# ArduinoShield.net
KiCad netlist of a schematic drawn in EAGLE
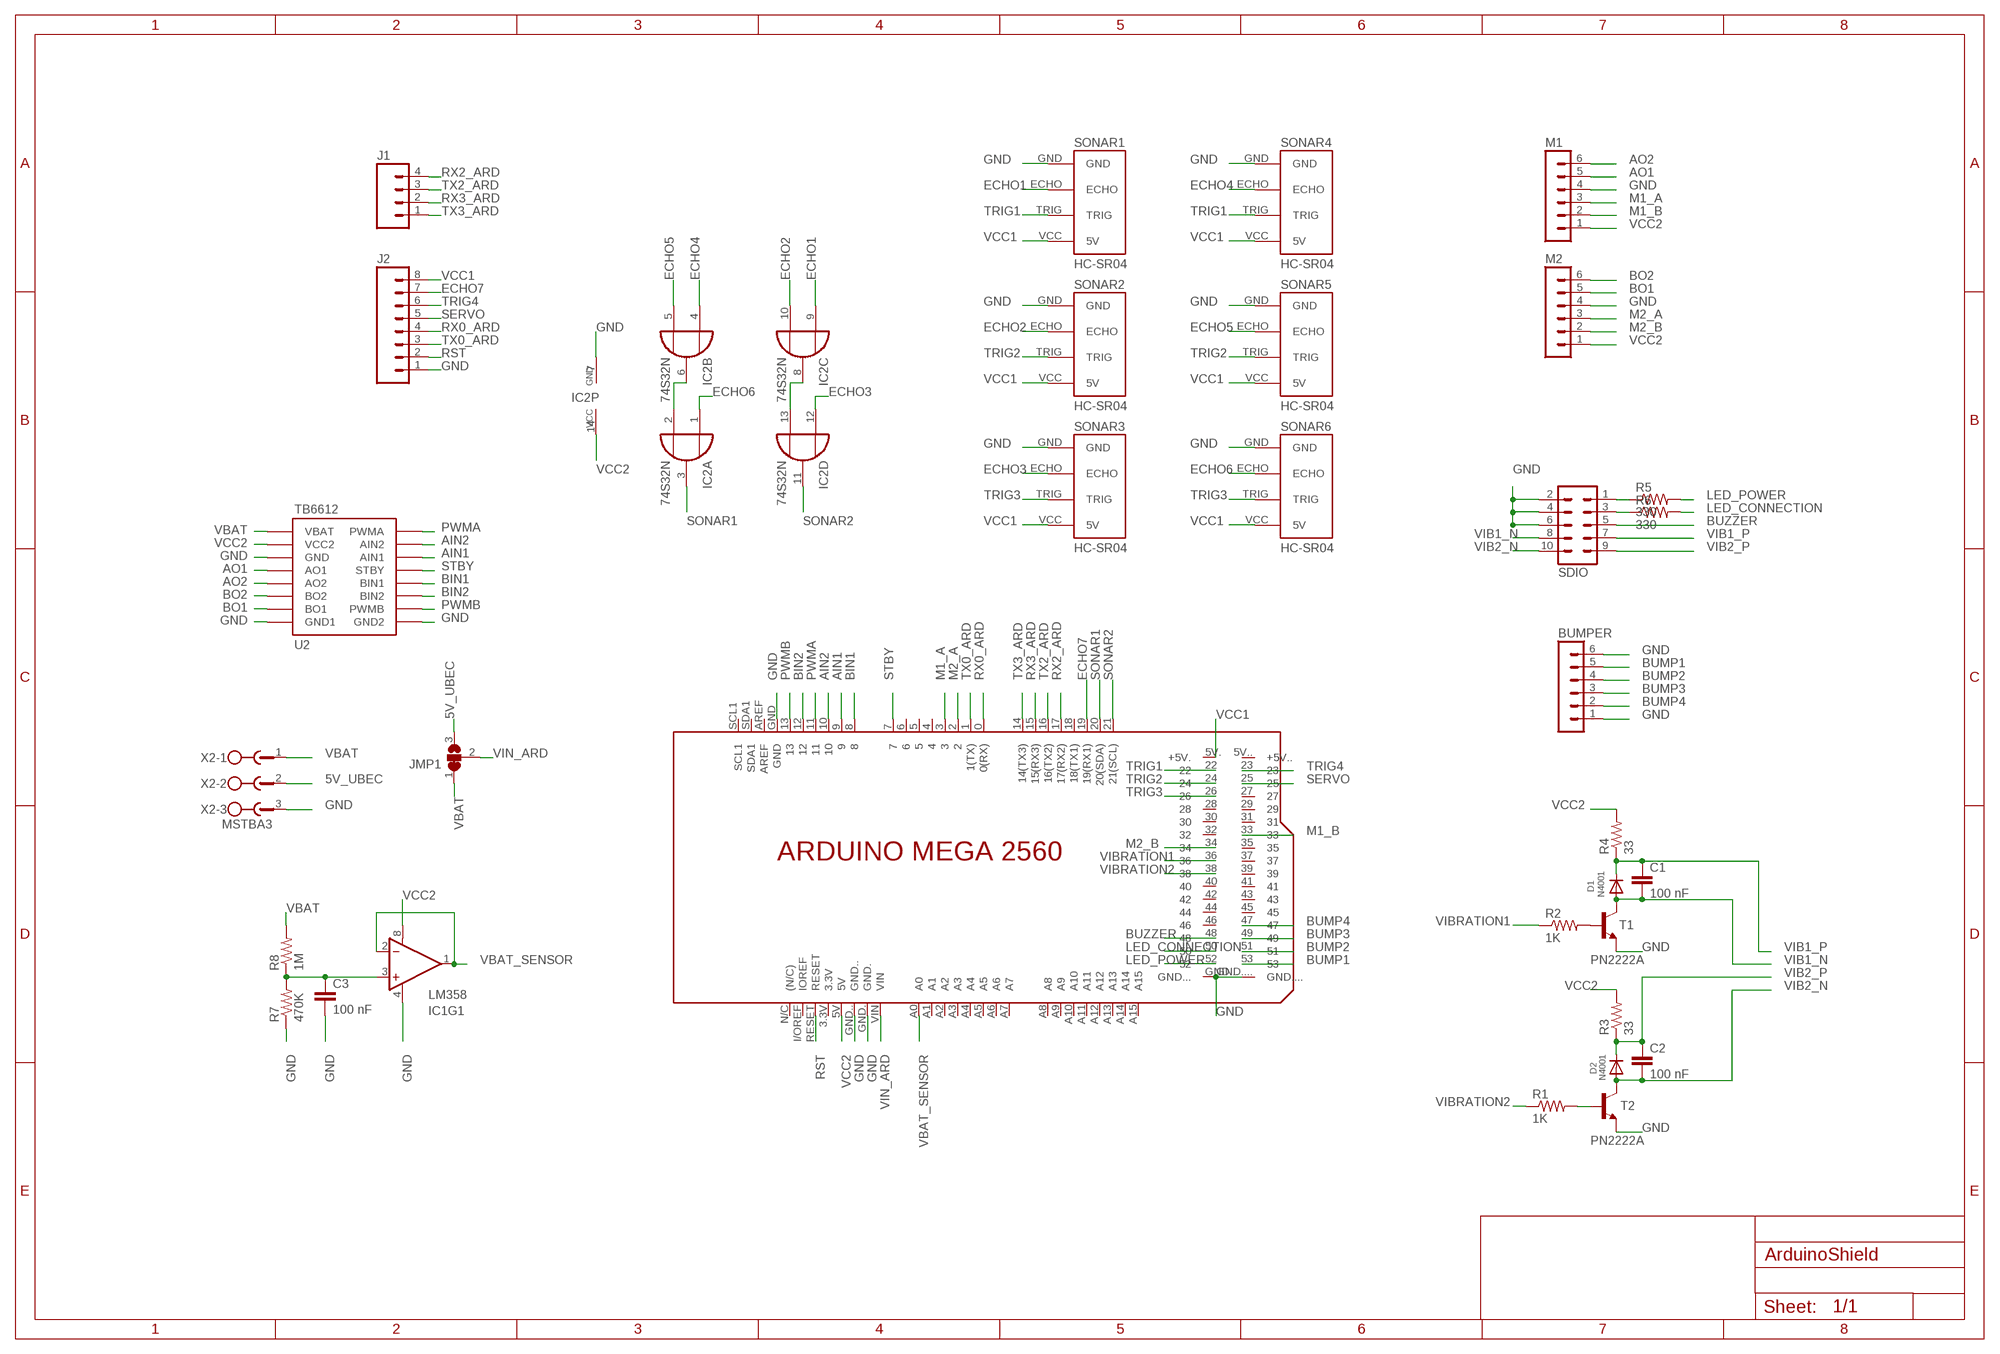
[diagram p0: schematic, sheet 1]

(export (version "E")
  (design (tool "Eeschema 10.0.6"))
  (components
    (comp (ref "BUMPER")
      (value "MA06-1")
      (footprint "eagle-import:MA06-1")
      (libsource (lib "eagle-import") (part "MA06-1"))
    )
    (comp (ref "C1")
      (value "100 nF")
      (footprint "eagle-import:C5B2.5")
      (libsource (lib "eagle-import") (part "C5/2.5"))
    )
    (comp (ref "C2")
      (value "100 nF")
      (footprint "eagle-import:C5B2.5")
      (libsource (lib "eagle-import") (part "C5/2.5"))
    )
    (comp (ref "C3")
      (value "100 nF")
      (footprint "eagle-import:C5B2.5")
      (libsource (lib "eagle-import") (part "C5/2.5"))
    )
    (comp (ref "D1")
      (value "N4001")
      (footprint "eagle-import:DO-1N4148")
      (libsource (lib "eagle-import") (part "DIODEDO-1N4148"))
    )
    (comp (ref "D2")
      (value "N4001")
      (footprint "eagle-import:DO-1N4148")
      (libsource (lib "eagle-import") (part "DIODEDO-1N4148"))
    )
    (comp (ref "IC1")
      (value "LM358")
      (footprint "eagle-import:DIP08")
      (libsource (lib "eagle-import") (part "LM358"))
    )
    (comp (ref "IC2")
      (value "74S32N")
      (footprint "eagle-import:DIL14")
      (libsource (lib "eagle-import") (part "7432NS"))
    )
    (comp (ref "J1")
      (value "M04PTH")
      (footprint "eagle-import:1X04")
      (libsource (lib "eagle-import") (part "M04PTH"))
    )
    (comp (ref "J2")
      (value "M08SILK_FEMALE_PTH")
      (footprint "eagle-import:1X08")
      (libsource (lib "eagle-import") (part "M08SILK_FEMALE_PTH"))
    )
    (comp (ref "JMP1")
      (value "SJ2W")
      (footprint "eagle-import:SJ_2")
      (libsource (lib "eagle-import") (part "SJ2W"))
    )
    (comp (ref "M1")
      (value "MA06-1")
      (footprint "eagle-import:MA06-1")
      (libsource (lib "eagle-import") (part "MA06-1"))
    )
    (comp (ref "M2")
      (value "MA06-1")
      (footprint "eagle-import:MA06-1")
      (libsource (lib "eagle-import") (part "MA06-1"))
    )
    (comp (ref "PCB1")
      (value "ARDUINO_MEGA2560")
      (footprint "eagle-import:ARDUINO_MEGA2560")
      (libsource (lib "eagle-import") (part "ARDUINO_MEGA2560"))
    )
    (comp (ref "R1")
      (value "1K")
      (footprint "eagle-import:0207_2V")
      (libsource (lib "eagle-import") (part "R-US_0207/2V"))
    )
    (comp (ref "R2")
      (value "1K")
      (footprint "eagle-import:0207_2V")
      (libsource (lib "eagle-import") (part "R-US_0207/2V"))
    )
    (comp (ref "R3")
      (value "33")
      (footprint "eagle-import:0207_2V")
      (libsource (lib "eagle-import") (part "R-US_0207/2V"))
    )
    (comp (ref "R4")
      (value "33")
      (footprint "eagle-import:0207_2V")
      (libsource (lib "eagle-import") (part "R-US_0207/2V"))
    )
    (comp (ref "R5")
      (value "330")
      (footprint "eagle-import:0207_2V")
      (libsource (lib "eagle-import") (part "R-US_0207/2V"))
    )
    (comp (ref "R6")
      (value "330")
      (footprint "eagle-import:0207_2V")
      (libsource (lib "eagle-import") (part "R-US_0207/2V"))
    )
    (comp (ref "R7")
      (value "470K")
      (footprint "eagle-import:0207_2V")
      (libsource (lib "eagle-import") (part "R-US_0207/2V"))
    )
    (comp (ref "R8")
      (value "1M")
      (footprint "eagle-import:0207_2V")
      (libsource (lib "eagle-import") (part "R-US_0207/2V"))
    )
    (comp (ref "SDIO")
      (value "MA05-2")
      (footprint "eagle-import:MA05-2")
      (libsource (lib "eagle-import") (part "MA05-2"))
    )
    (comp (ref "SONAR1")
      (value "HC-SR04")
      (footprint "eagle-import:HC-SR04_FOOTPRINT")
      (libsource (lib "eagle-import") (part "HC-SR04"))
    )
    (comp (ref "SONAR2")
      (value "HC-SR04")
      (footprint "eagle-import:HC-SR04_FOOTPRINT")
      (libsource (lib "eagle-import") (part "HC-SR04"))
    )
    (comp (ref "SONAR3")
      (value "HC-SR04")
      (footprint "eagle-import:HC-SR04_FOOTPRINT")
      (libsource (lib "eagle-import") (part "HC-SR04"))
    )
    (comp (ref "SONAR4")
      (value "HC-SR04")
      (footprint "eagle-import:HC-SR04_FOOTPRINT")
      (libsource (lib "eagle-import") (part "HC-SR04"))
    )
    (comp (ref "SONAR5")
      (value "HC-SR04")
      (footprint "eagle-import:HC-SR04_FOOTPRINT")
      (libsource (lib "eagle-import") (part "HC-SR04"))
    )
    (comp (ref "SONAR6")
      (value "HC-SR04")
      (footprint "eagle-import:HC-SR04_FOOTPRINT")
      (libsource (lib "eagle-import") (part "HC-SR04"))
    )
    (comp (ref "T1")
      (value "PN2222A")
      (footprint "eagle-import:TO92-EBC-OVAL")
      (libsource (lib "eagle-import") (part "2N2222"))
    )
    (comp (ref "T2")
      (value "PN2222A")
      (footprint "eagle-import:TO92-EBC-OVAL")
      (libsource (lib "eagle-import") (part "2N2222"))
    )
    (comp (ref "U2")
      (value "TB6612")
      (footprint "eagle-import:TB6612")
      (libsource (lib "eagle-import") (part "TB6612"))
    )
    (comp (ref "X2")
      (value "MSTBA3")
      (footprint "eagle-import:MSTBA3")
      (fields (field (name "MF") "FARNELL") (field (name "MPN") "1757255"))
      (libsource (lib "eagle-import") (part "MSTBA3"))
    )
  )
  (nets
    (net (code "1") (name "/5V_UBEC") (class "Default")
      (node (ref "JMP1") (pin "3") (pinfunction "3_3") (pintype "passive"))
      (node (ref "X2") (pin "2") (pinfunction "1_2") (pintype "passive"))
    )
    (net (code "2") (name "/AIN1") (class "Default")
      (node (ref "PCB1") (pin "9") (pinfunction "9_9") (pintype "bidirectional"))
      (node (ref "U2") (pin "P$14") (pinfunction "AIN1_P$14") (pintype "bidirectional"))
    )
    (net (code "3") (name "/AIN2") (class "Default")
      (node (ref "PCB1") (pin "10") (pinfunction "10_10") (pintype "bidirectional"))
      (node (ref "U2") (pin "P$15") (pinfunction "AIN2_P$15") (pintype "bidirectional"))
    )
    (net (code "4") (name "/AO1") (class "Default")
      (node (ref "M1") (pin "5") (pinfunction "5_5") (pintype "passive"))
      (node (ref "U2") (pin "P$4") (pinfunction "AO1_P$4") (pintype "bidirectional"))
    )
    (net (code "5") (name "/AO2") (class "Default")
      (node (ref "M1") (pin "6") (pinfunction "6_6") (pintype "passive"))
      (node (ref "U2") (pin "P$5") (pinfunction "AO2_P$5") (pintype "bidirectional"))
    )
    (net (code "6") (name "/BIN1") (class "Default")
      (node (ref "PCB1") (pin "8") (pinfunction "8_8") (pintype "bidirectional"))
      (node (ref "U2") (pin "P$12") (pinfunction "BIN1_P$12") (pintype "bidirectional"))
    )
    (net (code "7") (name "/BIN2") (class "Default")
      (node (ref "PCB1") (pin "12") (pinfunction "12_12") (pintype "bidirectional"))
      (node (ref "U2") (pin "P$11") (pinfunction "BIN2_P$11") (pintype "bidirectional"))
    )
    (net (code "8") (name "/BO1") (class "Default")
      (node (ref "M2") (pin "5") (pinfunction "5_5") (pintype "passive"))
      (node (ref "U2") (pin "P$7") (pinfunction "BO1_P$7") (pintype "bidirectional"))
    )
    (net (code "9") (name "/BO2") (class "Default")
      (node (ref "M2") (pin "6") (pinfunction "6_6") (pintype "passive"))
      (node (ref "U2") (pin "P$6") (pinfunction "BO2_P$6") (pintype "bidirectional"))
    )
    (net (code "10") (name "/BUMP1") (class "Default")
      (node (ref "BUMPER") (pin "5") (pinfunction "5_5") (pintype "passive"))
      (node (ref "PCB1") (pin "53") (pinfunction "53_53") (pintype "bidirectional"))
    )
    (net (code "11") (name "/BUMP2") (class "Default")
      (node (ref "BUMPER") (pin "4") (pinfunction "4_4") (pintype "passive"))
      (node (ref "PCB1") (pin "51") (pinfunction "51_51") (pintype "bidirectional"))
    )
    (net (code "12") (name "/BUMP3") (class "Default")
      (node (ref "BUMPER") (pin "3") (pinfunction "3_3") (pintype "passive"))
      (node (ref "PCB1") (pin "49") (pinfunction "49_49") (pintype "bidirectional"))
    )
    (net (code "13") (name "/BUMP4") (class "Default")
      (node (ref "BUMPER") (pin "2") (pinfunction "2_2") (pintype "passive"))
      (node (ref "PCB1") (pin "47") (pinfunction "47_47") (pintype "bidirectional"))
    )
    (net (code "14") (name "/BUZZER") (class "Default")
      (node (ref "PCB1") (pin "48") (pinfunction "48_48") (pintype "bidirectional"))
      (node (ref "SDIO") (pin "5") (pinfunction "5_5") (pintype "passive"))
    )
    (net (code "15") (name "/ECHO1") (class "Default")
      (node (ref "IC2") (pin "9") (pinfunction "I0_9") (pintype "input"))
      (node (ref "SONAR1") (pin "ECHO") (pinfunction "ECHO_ECHO") (pintype "bidirectional"))
    )
    (net (code "16") (name "/ECHO2") (class "Default")
      (node (ref "IC2") (pin "10") (pinfunction "I1_10") (pintype "input"))
      (node (ref "SONAR2") (pin "ECHO") (pinfunction "ECHO_ECHO") (pintype "bidirectional"))
    )
    (net (code "17") (name "/ECHO3") (class "Default")
      (node (ref "IC2") (pin "12") (pinfunction "I0_12") (pintype "input"))
      (node (ref "SONAR3") (pin "ECHO") (pinfunction "ECHO_ECHO") (pintype "bidirectional"))
    )
    (net (code "18") (name "/ECHO4") (class "Default")
      (node (ref "IC2") (pin "4") (pinfunction "I0_4") (pintype "input"))
      (node (ref "SONAR4") (pin "ECHO") (pinfunction "ECHO_ECHO") (pintype "bidirectional"))
    )
    (net (code "19") (name "/ECHO5") (class "Default")
      (node (ref "IC2") (pin "5") (pinfunction "I1_5") (pintype "input"))
      (node (ref "SONAR5") (pin "ECHO") (pinfunction "ECHO_ECHO") (pintype "bidirectional"))
    )
    (net (code "20") (name "/ECHO6") (class "Default")
      (node (ref "IC2") (pin "1") (pinfunction "I0_1") (pintype "input"))
      (node (ref "SONAR6") (pin "ECHO") (pinfunction "ECHO_ECHO") (pintype "bidirectional"))
    )
    (net (code "21") (name "/ECHO7") (class "Default")
      (node (ref "J2") (pin "7") (pinfunction "7_7") (pintype "passive"))
      (node (ref "PCB1") (pin "19") (pinfunction "19(RX1)_19") (pintype "bidirectional"))
    )
    (net (code "22") (name "/GND") (class "Default")
      (node (ref "BUMPER") (pin "1") (pinfunction "1_1") (pintype "passive"))
      (node (ref "BUMPER") (pin "6") (pinfunction "6_6") (pintype "passive"))
      (node (ref "C3") (pin "2") (pinfunction "2_2") (pintype "passive"))
      (node (ref "IC1") (pin "4") (pinfunction "V-_4") (pintype "power_in"))
      (node (ref "IC2") (pin "7") (pinfunction "GND_7") (pintype "power_in"))
      (node (ref "J2") (pin "1") (pinfunction "1_1") (pintype "passive"))
      (node (ref "M1") (pin "4") (pinfunction "4_4") (pintype "passive"))
      (node (ref "M2") (pin "4") (pinfunction "4_4") (pintype "passive"))
      (node (ref "PCB1") (pin "GND") (pinfunction "GND_GND") (pintype "bidirectional"))
      (node (ref "PCB1") (pin "GND.") (pinfunction "GND._GND.") (pintype "bidirectional"))
      (node (ref "PCB1") (pin "GND..") (pinfunction "GND.._GND..") (pintype "bidirectional"))
      (node (ref "PCB1") (pin "GND...") (pinfunction "GND..._GND...") (pintype "bidirectional"))
      (node (ref "PCB1") (pin "GND....") (pinfunction "GND...._GND....") (pintype "bidirectional"))
      (node (ref "R7") (pin "1") (pinfunction "1_1") (pintype "passive"))
      (node (ref "SDIO") (pin "2") (pinfunction "2_2") (pintype "passive"))
      (node (ref "SDIO") (pin "4") (pinfunction "4_4") (pintype "passive"))
      (node (ref "SDIO") (pin "6") (pinfunction "6_6") (pintype "passive"))
      (node (ref "SONAR1") (pin "GND") (pinfunction "GND_GND") (pintype "bidirectional"))
      (node (ref "SONAR2") (pin "GND") (pinfunction "GND_GND") (pintype "bidirectional"))
      (node (ref "SONAR3") (pin "GND") (pinfunction "GND_GND") (pintype "bidirectional"))
      (node (ref "SONAR4") (pin "GND") (pinfunction "GND_GND") (pintype "bidirectional"))
      (node (ref "SONAR5") (pin "GND") (pinfunction "GND_GND") (pintype "bidirectional"))
      (node (ref "SONAR6") (pin "GND") (pinfunction "GND_GND") (pintype "bidirectional"))
      (node (ref "T1") (pin "E") (pinfunction "E_E") (pintype "passive"))
      (node (ref "T2") (pin "E") (pinfunction "E_E") (pintype "passive"))
      (node (ref "U2") (pin "P$3") (pinfunction "GND_P$3") (pintype "bidirectional"))
      (node (ref "U2") (pin "P$8") (pinfunction "GND1_P$8") (pintype "bidirectional"))
      (node (ref "U2") (pin "P$9") (pinfunction "GND2_P$9") (pintype "bidirectional"))
      (node (ref "X2") (pin "3") (pinfunction "1_3") (pintype "passive"))
    )
    (net (code "23") (name "/LED_CONNECTION") (class "Default")
      (node (ref "PCB1") (pin "50") (pinfunction "50_50") (pintype "bidirectional"))
      (node (ref "R6") (pin "2") (pinfunction "2_2") (pintype "passive"))
    )
    (net (code "24") (name "/LED_POWER") (class "Default")
      (node (ref "PCB1") (pin "52") (pinfunction "52_52") (pintype "bidirectional"))
      (node (ref "R5") (pin "2") (pinfunction "2_2") (pintype "passive"))
    )
    (net (code "25") (name "/M1_A") (class "Default")
      (node (ref "M1") (pin "3") (pinfunction "3_3") (pintype "passive"))
      (node (ref "PCB1") (pin "3") (pinfunction "3_3") (pintype "bidirectional"))
    )
    (net (code "26") (name "/M1_B") (class "Default")
      (node (ref "M1") (pin "2") (pinfunction "2_2") (pintype "passive"))
      (node (ref "PCB1") (pin "33") (pinfunction "33_33") (pintype "bidirectional"))
    )
    (net (code "27") (name "/M2_A") (class "Default")
      (node (ref "M2") (pin "3") (pinfunction "3_3") (pintype "passive"))
      (node (ref "PCB1") (pin "2") (pinfunction "2_2") (pintype "bidirectional"))
    )
    (net (code "28") (name "/M2_B") (class "Default")
      (node (ref "M2") (pin "2") (pinfunction "2_2") (pintype "passive"))
      (node (ref "PCB1") (pin "34") (pinfunction "34_34") (pintype "bidirectional"))
    )
    (net (code "29") (name "/PWMA") (class "Default")
      (node (ref "PCB1") (pin "11") (pinfunction "11_11") (pintype "bidirectional"))
      (node (ref "U2") (pin "P$16") (pinfunction "PWMA_P$16") (pintype "bidirectional"))
    )
    (net (code "30") (name "/PWMB") (class "Default")
      (node (ref "PCB1") (pin "13") (pinfunction "13_13") (pintype "bidirectional"))
      (node (ref "U2") (pin "P$10") (pinfunction "PWMB_P$10") (pintype "bidirectional"))
    )
    (net (code "31") (name "/RST") (class "Default")
      (node (ref "J2") (pin "2") (pinfunction "2_2") (pintype "passive"))
      (node (ref "PCB1") (pin "RESET") (pinfunction "RESET_RESET") (pintype "bidirectional"))
    )
    (net (code "32") (name "/RX0_ARD") (class "Default")
      (node (ref "J2") (pin "4") (pinfunction "4_4") (pintype "passive"))
      (node (ref "PCB1") (pin "0") (pinfunction "0(RX)_0") (pintype "bidirectional"))
    )
    (net (code "33") (name "/RX2_ARD") (class "Default")
      (node (ref "J1") (pin "4") (pinfunction "4_4") (pintype "passive"))
      (node (ref "PCB1") (pin "17") (pinfunction "17(RX2)_17") (pintype "bidirectional"))
    )
    (net (code "34") (name "/RX3_ARD") (class "Default")
      (node (ref "J1") (pin "2") (pinfunction "2_2") (pintype "passive"))
      (node (ref "PCB1") (pin "15") (pinfunction "15(RX3)_15") (pintype "bidirectional"))
    )
    (net (code "35") (name "/SERVO") (class "Default")
      (node (ref "J2") (pin "5") (pinfunction "5_5") (pintype "passive"))
      (node (ref "PCB1") (pin "25") (pinfunction "25_25") (pintype "bidirectional"))
    )
    (net (code "36") (name "/SONAR1") (class "Default")
      (node (ref "IC2") (pin "3") (pinfunction "O_3") (pintype "output"))
      (node (ref "PCB1") (pin "20") (pinfunction "20(SDA)_20") (pintype "bidirectional"))
    )
    (net (code "37") (name "/SONAR2") (class "Default")
      (node (ref "IC2") (pin "11") (pinfunction "O_11") (pintype "output"))
      (node (ref "PCB1") (pin "21") (pinfunction "21(SCL)_21") (pintype "bidirectional"))
    )
    (net (code "38") (name "/STBY") (class "Default")
      (node (ref "PCB1") (pin "7") (pinfunction "7_7") (pintype "bidirectional"))
      (node (ref "U2") (pin "P$13") (pinfunction "STBY_P$13") (pintype "bidirectional"))
    )
    (net (code "39") (name "/TRIG1") (class "Default")
      (node (ref "PCB1") (pin "22") (pinfunction "22_22") (pintype "bidirectional"))
      (node (ref "SONAR1") (pin "TRIG") (pinfunction "TRIG_TRIG") (pintype "bidirectional"))
      (node (ref "SONAR4") (pin "TRIG") (pinfunction "TRIG_TRIG") (pintype "bidirectional"))
    )
    (net (code "40") (name "/TRIG2") (class "Default")
      (node (ref "PCB1") (pin "24") (pinfunction "24_24") (pintype "bidirectional"))
      (node (ref "SONAR2") (pin "TRIG") (pinfunction "TRIG_TRIG") (pintype "bidirectional"))
      (node (ref "SONAR5") (pin "TRIG") (pinfunction "TRIG_TRIG") (pintype "bidirectional"))
    )
    (net (code "41") (name "/TRIG3") (class "Default")
      (node (ref "PCB1") (pin "26") (pinfunction "26_26") (pintype "bidirectional"))
      (node (ref "SONAR3") (pin "TRIG") (pinfunction "TRIG_TRIG") (pintype "bidirectional"))
      (node (ref "SONAR6") (pin "TRIG") (pinfunction "TRIG_TRIG") (pintype "bidirectional"))
    )
    (net (code "42") (name "/TRIG4") (class "Default")
      (node (ref "J2") (pin "6") (pinfunction "6_6") (pintype "passive"))
      (node (ref "PCB1") (pin "23") (pinfunction "23_23") (pintype "bidirectional"))
    )
    (net (code "43") (name "/TX0_ARD") (class "Default")
      (node (ref "J2") (pin "3") (pinfunction "3_3") (pintype "passive"))
      (node (ref "PCB1") (pin "1") (pinfunction "1(TX)_1") (pintype "bidirectional"))
    )
    (net (code "44") (name "/TX2_ARD") (class "Default")
      (node (ref "J1") (pin "3") (pinfunction "3_3") (pintype "passive"))
      (node (ref "PCB1") (pin "16") (pinfunction "16(TX2)_16") (pintype "bidirectional"))
    )
    (net (code "45") (name "/TX3_ARD") (class "Default")
      (node (ref "J1") (pin "1") (pinfunction "1_1") (pintype "passive"))
      (node (ref "PCB1") (pin "14") (pinfunction "14(TX3)_14") (pintype "bidirectional"))
    )
    (net (code "46") (name "/VBAT") (class "Default")
      (node (ref "JMP1") (pin "1") (pinfunction "1_1") (pintype "passive"))
      (node (ref "R8") (pin "2") (pinfunction "2_2") (pintype "passive"))
      (node (ref "U2") (pin "P$1") (pinfunction "VBAT_P$1") (pintype "bidirectional"))
      (node (ref "X2") (pin "1") (pinfunction "1_1") (pintype "passive"))
    )
    (net (code "47") (name "/VBAT_SENSOR") (class "Default")
      (node (ref "IC1") (pin "1") (pinfunction "OUT_1") (pintype "output"))
      (node (ref "IC1") (pin "2") (pinfunction "-IN_2") (pintype "input"))
      (node (ref "PCB1") (pin "A0") (pinfunction "A0_A0") (pintype "bidirectional"))
    )
    (net (code "48") (name "/VCC1") (class "Default")
      (node (ref "J2") (pin "8") (pinfunction "8_8") (pintype "passive"))
      (node (ref "PCB1") (pin "5V.") (pinfunction "+5V._5V.") (pintype "bidirectional"))
      (node (ref "SONAR1") (pin "VCC") (pinfunction "5V_VCC") (pintype "bidirectional"))
      (node (ref "SONAR2") (pin "VCC") (pinfunction "5V_VCC") (pintype "bidirectional"))
      (node (ref "SONAR3") (pin "VCC") (pinfunction "5V_VCC") (pintype "bidirectional"))
      (node (ref "SONAR4") (pin "VCC") (pinfunction "5V_VCC") (pintype "bidirectional"))
      (node (ref "SONAR5") (pin "VCC") (pinfunction "5V_VCC") (pintype "bidirectional"))
      (node (ref "SONAR6") (pin "VCC") (pinfunction "5V_VCC") (pintype "bidirectional"))
    )
    (net (code "49") (name "/VCC2") (class "Default")
      (node (ref "IC1") (pin "8") (pinfunction "V+_8") (pintype "power_in"))
      (node (ref "IC2") (pin "14") (pinfunction "VCC_14") (pintype "power_in"))
      (node (ref "M1") (pin "1") (pinfunction "1_1") (pintype "passive"))
      (node (ref "M2") (pin "1") (pinfunction "1_1") (pintype "passive"))
      (node (ref "PCB1") (pin "5V") (pinfunction "5V_5V") (pintype "bidirectional"))
      (node (ref "R3") (pin "2") (pinfunction "2_2") (pintype "passive"))
      (node (ref "R4") (pin "2") (pinfunction "2_2") (pintype "passive"))
      (node (ref "U2") (pin "P$2") (pinfunction "VCC2_P$2") (pintype "bidirectional"))
    )
    (net (code "50") (name "/VIB1_N") (class "Default")
      (node (ref "C1") (pin "2") (pinfunction "2_2") (pintype "passive"))
      (node (ref "D1") (pin "A") (pinfunction "A_A") (pintype "passive"))
      (node (ref "SDIO") (pin "8") (pinfunction "8_8") (pintype "passive"))
      (node (ref "T1") (pin "C") (pinfunction "C_C") (pintype "passive"))
    )
    (net (code "51") (name "/VIB1_P") (class "Default")
      (node (ref "C1") (pin "1") (pinfunction "1_1") (pintype "passive"))
      (node (ref "D1") (pin "C") (pinfunction "C_C") (pintype "passive"))
      (node (ref "R4") (pin "1") (pinfunction "1_1") (pintype "passive"))
      (node (ref "SDIO") (pin "7") (pinfunction "7_7") (pintype "passive"))
    )
    (net (code "52") (name "/VIB2_N") (class "Default")
      (node (ref "C2") (pin "2") (pinfunction "2_2") (pintype "passive"))
      (node (ref "D2") (pin "A") (pinfunction "A_A") (pintype "passive"))
      (node (ref "SDIO") (pin "10") (pinfunction "10_10") (pintype "passive"))
      (node (ref "T2") (pin "C") (pinfunction "C_C") (pintype "passive"))
    )
    (net (code "53") (name "/VIB2_P") (class "Default")
      (node (ref "C2") (pin "1") (pinfunction "1_1") (pintype "passive"))
      (node (ref "D2") (pin "C") (pinfunction "C_C") (pintype "passive"))
      (node (ref "R3") (pin "1") (pinfunction "1_1") (pintype "passive"))
      (node (ref "SDIO") (pin "9") (pinfunction "9_9") (pintype "passive"))
    )
    (net (code "54") (name "/VIBRATION1") (class "Default")
      (node (ref "PCB1") (pin "36") (pinfunction "36_36") (pintype "bidirectional"))
      (node (ref "R2") (pin "1") (pinfunction "1_1") (pintype "passive"))
    )
    (net (code "55") (name "/VIBRATION2") (class "Default")
      (node (ref "PCB1") (pin "38") (pinfunction "38_38") (pintype "bidirectional"))
      (node (ref "R1") (pin "1") (pinfunction "1_1") (pintype "passive"))
    )
    (net (code "56") (name "/VIN_ARD") (class "Default")
      (node (ref "JMP1") (pin "2") (pinfunction "2_2") (pintype "passive"))
      (node (ref "PCB1") (pin "VIN") (pinfunction "VIN_VIN") (pintype "bidirectional"))
    )
    (net (code "57") (name "Net-(IC1A-+IN)") (class "Default")
      (node (ref "C3") (pin "1") (pinfunction "1_1") (pintype "passive"))
      (node (ref "IC1") (pin "3") (pinfunction "+IN_3") (pintype "input"))
      (node (ref "R7") (pin "2") (pinfunction "2_2") (pintype "passive"))
      (node (ref "R8") (pin "1") (pinfunction "1_1") (pintype "passive"))
    )
    (net (code "58") (name "Net-(IC2A-I1)") (class "Default")
      (node (ref "IC2") (pin "2") (pinfunction "I1_2") (pintype "input"))
      (node (ref "IC2") (pin "6") (pinfunction "O_6") (pintype "output"))
    )
    (net (code "59") (name "Net-(IC2C-O)") (class "Default")
      (node (ref "IC2") (pin "13") (pinfunction "I1_13") (pintype "input"))
      (node (ref "IC2") (pin "8") (pinfunction "O_8") (pintype "output"))
    )
    (net (code "60") (name "Net-(R1-Pad2)") (class "Default")
      (node (ref "R1") (pin "2") (pinfunction "2_2") (pintype "passive"))
      (node (ref "T2") (pin "B") (pinfunction "B_B") (pintype "passive"))
    )
    (net (code "61") (name "Net-(R2-Pad2)") (class "Default")
      (node (ref "R2") (pin "2") (pinfunction "2_2") (pintype "passive"))
      (node (ref "T1") (pin "B") (pinfunction "B_B") (pintype "passive"))
    )
    (net (code "62") (name "Net-(R5-Pad1)") (class "Default")
      (node (ref "R5") (pin "1") (pinfunction "1_1") (pintype "passive"))
      (node (ref "SDIO") (pin "1") (pinfunction "1_1") (pintype "passive"))
    )
    (net (code "63") (name "Net-(R6-Pad1)") (class "Default")
      (node (ref "R6") (pin "1") (pinfunction "1_1") (pintype "passive"))
      (node (ref "SDIO") (pin "3") (pinfunction "3_3") (pintype "passive"))
    )
    (net (code "64") (name "unconnected-(PCB1-(N{slash}C)-PadN{slash}C)") (class "Default")
      (node (ref "PCB1") (pin "N/C") (pinfunction "(N/C)_N/C") (pintype "bidirectional"))
    )
    (net (code "65") (name "unconnected-(PCB1-+5V..-Pad5V..)") (class "Default")
      (node (ref "PCB1") (pin "5V..") (pinfunction "+5V.._5V..") (pintype "bidirectional"))
    )
    (net (code "66") (name "unconnected-(PCB1-18(TX1)-Pad18)") (class "Default")
      (node (ref "PCB1") (pin "18") (pinfunction "18(TX1)_18") (pintype "bidirectional"))
    )
    (net (code "67") (name "unconnected-(PCB1-IOREF-PadI{slash}OREF)") (class "Default")
      (node (ref "PCB1") (pin "I/OREF") (pinfunction "IOREF_I/OREF") (pintype "bidirectional"))
    )
    (net (code "68") (name "unconnected-(PCB1-Pad3.3V)") (class "Default")
      (node (ref "PCB1") (pin "3.3V") (pinfunction "3.3V_3.3V") (pintype "bidirectional"))
    )
    (net (code "69") (name "unconnected-(PCB1-Pad4)") (class "Default")
      (node (ref "PCB1") (pin "4") (pinfunction "4_4") (pintype "bidirectional"))
    )
    (net (code "70") (name "unconnected-(PCB1-Pad5)") (class "Default")
      (node (ref "PCB1") (pin "5") (pinfunction "5_5") (pintype "bidirectional"))
    )
    (net (code "71") (name "unconnected-(PCB1-Pad6)") (class "Default")
      (node (ref "PCB1") (pin "6") (pinfunction "6_6") (pintype "bidirectional"))
    )
    (net (code "72") (name "unconnected-(PCB1-Pad27)") (class "Default")
      (node (ref "PCB1") (pin "27") (pinfunction "27_27") (pintype "bidirectional"))
    )
    (net (code "73") (name "unconnected-(PCB1-Pad28)") (class "Default")
      (node (ref "PCB1") (pin "28") (pinfunction "28_28") (pintype "bidirectional"))
    )
    (net (code "74") (name "unconnected-(PCB1-Pad29)") (class "Default")
      (node (ref "PCB1") (pin "29") (pinfunction "29_29") (pintype "bidirectional"))
    )
    (net (code "75") (name "unconnected-(PCB1-Pad30)") (class "Default")
      (node (ref "PCB1") (pin "30") (pinfunction "30_30") (pintype "bidirectional"))
    )
    (net (code "76") (name "unconnected-(PCB1-Pad31)") (class "Default")
      (node (ref "PCB1") (pin "31") (pinfunction "31_31") (pintype "bidirectional"))
    )
    (net (code "77") (name "unconnected-(PCB1-Pad32)") (class "Default")
      (node (ref "PCB1") (pin "32") (pinfunction "32_32") (pintype "bidirectional"))
    )
    (net (code "78") (name "unconnected-(PCB1-Pad35)") (class "Default")
      (node (ref "PCB1") (pin "35") (pinfunction "35_35") (pintype "bidirectional"))
    )
    (net (code "79") (name "unconnected-(PCB1-Pad37)") (class "Default")
      (node (ref "PCB1") (pin "37") (pinfunction "37_37") (pintype "bidirectional"))
    )
    (net (code "80") (name "unconnected-(PCB1-Pad39)") (class "Default")
      (node (ref "PCB1") (pin "39") (pinfunction "39_39") (pintype "bidirectional"))
    )
    (net (code "81") (name "unconnected-(PCB1-Pad40)") (class "Default")
      (node (ref "PCB1") (pin "40") (pinfunction "40_40") (pintype "bidirectional"))
    )
    (net (code "82") (name "unconnected-(PCB1-Pad41)") (class "Default")
      (node (ref "PCB1") (pin "41") (pinfunction "41_41") (pintype "bidirectional"))
    )
    (net (code "83") (name "unconnected-(PCB1-Pad42)") (class "Default")
      (node (ref "PCB1") (pin "42") (pinfunction "42_42") (pintype "bidirectional"))
    )
    (net (code "84") (name "unconnected-(PCB1-Pad43)") (class "Default")
      (node (ref "PCB1") (pin "43") (pinfunction "43_43") (pintype "bidirectional"))
    )
    (net (code "85") (name "unconnected-(PCB1-Pad44)") (class "Default")
      (node (ref "PCB1") (pin "44") (pinfunction "44_44") (pintype "bidirectional"))
    )
    (net (code "86") (name "unconnected-(PCB1-Pad45)") (class "Default")
      (node (ref "PCB1") (pin "45") (pinfunction "45_45") (pintype "bidirectional"))
    )
    (net (code "87") (name "unconnected-(PCB1-Pad46)") (class "Default")
      (node (ref "PCB1") (pin "46") (pinfunction "46_46") (pintype "bidirectional"))
    )
    (net (code "88") (name "unconnected-(PCB1-PadA1)") (class "Default")
      (node (ref "PCB1") (pin "A1") (pinfunction "A1_A1") (pintype "bidirectional"))
    )
    (net (code "89") (name "unconnected-(PCB1-PadA2)") (class "Default")
      (node (ref "PCB1") (pin "A2") (pinfunction "A2_A2") (pintype "bidirectional"))
    )
    (net (code "90") (name "unconnected-(PCB1-PadA3)") (class "Default")
      (node (ref "PCB1") (pin "A3") (pinfunction "A3_A3") (pintype "bidirectional"))
    )
    (net (code "91") (name "unconnected-(PCB1-PadA4)") (class "Default")
      (node (ref "PCB1") (pin "A4") (pinfunction "A4_A4") (pintype "bidirectional"))
    )
    (net (code "92") (name "unconnected-(PCB1-PadA5)") (class "Default")
      (node (ref "PCB1") (pin "A5") (pinfunction "A5_A5") (pintype "bidirectional"))
    )
    (net (code "93") (name "unconnected-(PCB1-PadA6)") (class "Default")
      (node (ref "PCB1") (pin "A6") (pinfunction "A6_A6") (pintype "bidirectional"))
    )
    (net (code "94") (name "unconnected-(PCB1-PadA7)") (class "Default")
      (node (ref "PCB1") (pin "A7") (pinfunction "A7_A7") (pintype "bidirectional"))
    )
    (net (code "95") (name "unconnected-(PCB1-PadA8)") (class "Default")
      (node (ref "PCB1") (pin "A8") (pinfunction "A8_A8") (pintype "bidirectional"))
    )
    (net (code "96") (name "unconnected-(PCB1-PadA9)") (class "Default")
      (node (ref "PCB1") (pin "A9") (pinfunction "A9_A9") (pintype "bidirectional"))
    )
    (net (code "97") (name "unconnected-(PCB1-PadA10)") (class "Default")
      (node (ref "PCB1") (pin "A10") (pinfunction "A10_A10") (pintype "bidirectional"))
    )
    (net (code "98") (name "unconnected-(PCB1-PadA11)") (class "Default")
      (node (ref "PCB1") (pin "A11") (pinfunction "A11_A11") (pintype "bidirectional"))
    )
    (net (code "99") (name "unconnected-(PCB1-PadA12)") (class "Default")
      (node (ref "PCB1") (pin "A12") (pinfunction "A12_A12") (pintype "bidirectional"))
    )
    (net (code "100") (name "unconnected-(PCB1-PadA13)") (class "Default")
      (node (ref "PCB1") (pin "A13") (pinfunction "A13_A13") (pintype "bidirectional"))
    )
    (net (code "101") (name "unconnected-(PCB1-PadA14)") (class "Default")
      (node (ref "PCB1") (pin "A14") (pinfunction "A14_A14") (pintype "bidirectional"))
    )
    (net (code "102") (name "unconnected-(PCB1-PadA15)") (class "Default")
      (node (ref "PCB1") (pin "A15") (pinfunction "A15_A15") (pintype "bidirectional"))
    )
    (net (code "103") (name "unconnected-(PCB1-PadAREF)") (class "Default")
      (node (ref "PCB1") (pin "AREF") (pinfunction "AREF_AREF") (pintype "bidirectional"))
    )
    (net (code "104") (name "unconnected-(PCB1-PadSCL1)") (class "Default")
      (node (ref "PCB1") (pin "SCL1") (pinfunction "SCL1_SCL1") (pintype "bidirectional"))
    )
    (net (code "105") (name "unconnected-(PCB1-PadSDA1)") (class "Default")
      (node (ref "PCB1") (pin "SDA1") (pinfunction "SDA1_SDA1") (pintype "bidirectional"))
    )
  )
)
